# Gas_Sampler-Motor.net
KiCad netlist of a schematic drawn in Altium Designer
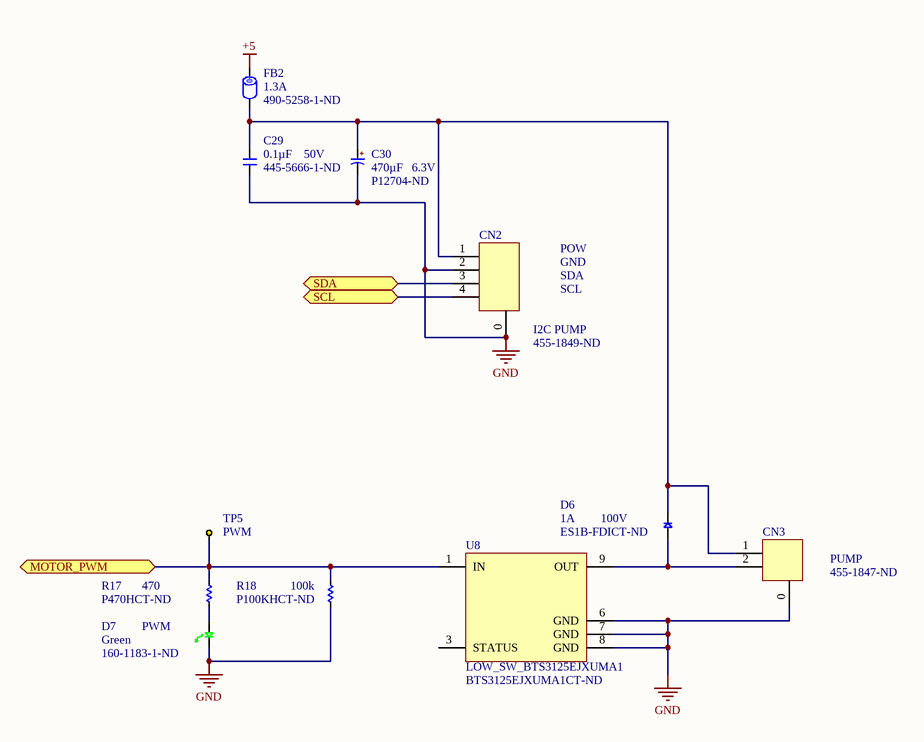
[diagram p0: Gas_Sampler-Motor.SchDoc]

(export (version "E")
  (design (tool "Eeschema 10.0.6"))
  (components
    (comp (ref "C29")
      (value "0.1µF")
      (footprint "C0603")
      (description "CAP CER 0.1UF 50V 10% X7R 0603")
      (fields
        (field (name "MANUFACTURER") "TDK Corporation")
        (field (name "MANUFACTURER PART NUMBER") "CGA3E2X7R1H104K080AA")
        (field (name "VOLTAGE - RATED") "50V")
        (field (name "SUPPLIER PART NUMBER 1") "445-5666-1-ND")
      )
      (libsource (lib "capacitor") (part "CAP_CER_0603_0.1UF_50V_10%_X7R"))
    )
    (comp (ref "C30")
      (value "470µF")
      (footprint "CAP_RADIAL_8MM_DIA_11.5MM_LEN_3.5MM_LEADSPACE")
      (description "CAP ALUM 470UF 6.3V 20% RADIAL")
      (fields
        (field (name "MANUFACTURER") "Panasonic Electronic Components")
        (field (name "MANUFACTURER PART NUMBER") "EEU-FC0J471")
        (field (name "VOLTAGE - RATED") "6.3V")
        (field (name "SUPPLIER PART NUMBER 1") "P12704-ND")
      )
      (libsource (lib "capacitor") (part "CAP_ALUM_470UF_6.3V_20%_RADIAL_8X11.5MM"))
    )
    (comp (ref "CN2")
      (value "I2C PUMP")
      (footprint "JST_PA_S04B-PASK-2")
      (description "CONN HEADER PA 4POS SIDE 2MM TIN")
      (fields
        (field (name "MANUFACTURER") "JST Sales America Inc.")
        (field (name "MANUFACTURER PART NUMBER") "S04B-PASK-2(LF)(SN)")
        (field (name "SUPPLIER PART NUMBER 1") "455-1849-ND")
      )
      (libsource (lib "jst pa") (part "JST_PA_RA_TH_GUIDE_4POS"))
    )
    (comp (ref "CN3")
      (value "PUMP")
      (footprint "JST_PA_S02B-PASK-2")
      (description "CONN HEADER PA 2POS SIDE 2MM TIN")
      (fields
        (field (name "MANUFACTURER") "JST Sales America Inc.")
        (field (name "MANUFACTURER PART NUMBER") "S02B-PASK-2(LF)(SN)")
        (field (name "SUPPLIER PART NUMBER 1") "455-1847-ND")
      )
      (libsource (lib "jst pa") (part "JST_PA_RA_TH_GUIDE_2POS"))
    )
    (comp (ref "D6")
      (value "DIODE_ES1B-FDICT-ND")
      (footprint "SMA")
      (description "DIODE SUPER FAST 100V 1A SMA")
      (fields
        (field (name "MANUFACTURER") "Diodes Inc")
        (field (name "MANUFACTURER PART NUMBER") "ES1B-13-F")
        (field (name "VOLTAGE - DC REVERSE (VR) (MAX)") "100V")
        (field (name "CURRENT - AVERAGE RECTIFIED (IO)") "1A")
        (field (name "SUPPLIER PART NUMBER 1") "ES1B-FDICT-ND")
      )
      (libsource (lib "diode") (part "DIODE_ES1B-FDICT-ND"))
    )
    (comp (ref "D7")
      (value "PWM")
      (footprint "LED_0603_GREEN")
      (description "LED GREEN CLEAR 0603 SMD")
      (fields
        (field (name "MANUFACTURER") "Lite-On Inc")
        (field (name "MANUFACTURER PART NUMBER") "LTST-C190GKT")
        (field (name "COLOR") "Green")
        (field (name "SUPPLIER PART NUMBER 1") "160-1183-1-ND")
      )
      (libsource (lib "diode") (part "LED_0603_GREEN_LG_LTST-C190GKT"))
    )
    (comp (ref "FB2")
      (value "FERRITE_BEAD_0603_1.3A_600_OHM")
      (footprint "R0603")
      (description "FERRITE BEAD 600 OHM 0603 1LN")
      (fields
        (field (name "MANUFACTURER") "Murata Electronics North America")
        (field (name "MANUFACTURER PART NUMBER") "BLM18KG601SN1D")
        (field (name "CURRENT RATING (MAX)") "1.3A")
        (field (name "SUPPLIER PART NUMBER 1") "490-5258-1-ND")
      )
      (libsource (lib "miscellaneous") (part "FERRITE_BEAD_0603_1.3A_600_OHM"))
    )
    (comp (ref "R17")
      (value "470")
      (footprint "R0603")
      (description "RES 470 OHM 1/10W 1% 0603 SMD")
      (fields
        (field (name "MANUFACTURER") "Panasonic Electronic Components")
        (field (name "MANUFACTURER PART NUMBER") "ERJ-3EKF4700V")
        (field (name "SUPPLIER PART NUMBER 1") "P470HCT-ND")
      )
      (libsource (lib "resistor") (part "RES_0603_470_OHM_1/10W_1%"))
    )
    (comp (ref "R18")
      (value "100k")
      (footprint "R0603")
      (description "RES 100K OHM 1/10W 1% 0603 SMD")
      (fields
        (field (name "MANUFACTURER") "Panasonic Electronic Components")
        (field (name "MANUFACTURER PART NUMBER") "ERJ-3EKF1003V")
        (field (name "SUPPLIER PART NUMBER 1") "P100KHCT-ND")
      )
      (libsource (lib "resistor") (part "RES_0603_100K_OHM_1/10W_1%"))
    )
    (comp (ref "TP5")
      (value "PWM")
      (footprint "TP_KEYSTONE_5001")
      (description "PC TEST POINT TH RING")
      (fields
        (field (name "MANUFACTURER") "Keystone Electronics")
        (field (name "MANUFACTURER PART NUMBER") "5001")
      )
      (libsource (lib "miscellaneous") (part "TEST_KEYSTONE5001"))
    )
    (comp (ref "U8")
      (value "LOW_SW_BTS3125EJXUMA1")
      (footprint "8SOIC150E")
      (description "IC PWR SWITCH N-CHAN 1:1 TDSO-8")
      (fields
        (field (name "MANUFACTURER") "Infineon Technologies")
        (field (name "MANUFACTURER PART NUMBER") "BTS3125EJXUMA1")
        (field (name "SUPPLIER PART NUMBER 1") "BTS3125EJXUMA1CT-ND")
      )
      (libsource (lib "ic_pmic") (part "LOW_SW_BTS3125EJXUMA1"))
    )
  )
  (nets
    (net (code "1") (name "+5") (class "Default")
      (node (ref "FB2") (pin "1") (pinfunction "1_1") (pintype "passive"))
    )
    (net (code "2") (name "/MOTOR_PWM") (class "Default")
      (node (ref "R17") (pin "2") (pintype "passive"))
      (node (ref "R18") (pin "2") (pintype "passive"))
      (node (ref "TP5") (pin "1") (pintype "passive"))
      (node (ref "U8") (pin "1") (pinfunction "IN_1") (pintype "passive"))
    )
    (net (code "3") (name "/SCL") (class "Default")
      (node (ref "CN2") (pin "4") (pinfunction "4_4") (pintype "passive"))
    )
    (net (code "4") (name "/SDA") (class "Default")
      (node (ref "CN2") (pin "3") (pinfunction "3_3") (pintype "passive"))
    )
    (net (code "5") (name "GND") (class "Default")
      (node (ref "C29") (pin "2") (pintype "passive"))
      (node (ref "C30") (pin "2") (pintype "passive"))
      (node (ref "CN2") (pin "0") (pinfunction "CHAS_0") (pintype "passive"))
      (node (ref "CN2") (pin "2") (pinfunction "2_2") (pintype "passive"))
      (node (ref "CN3") (pin "0") (pinfunction "CHAS_0") (pintype "passive"))
      (node (ref "D7") (pin "2") (pinfunction "CATHODE_2") (pintype "passive"))
      (node (ref "R18") (pin "1") (pintype "passive"))
      (node (ref "U8") (pin "6") (pinfunction "GND_6") (pintype "passive"))
      (node (ref "U8") (pin "7") (pinfunction "GND_7") (pintype "passive"))
      (node (ref "U8") (pin "8") (pinfunction "GND_8") (pintype "passive"))
    )
    (net (code "6") (name "Net-(C29-Pad1)") (class "Default")
      (node (ref "C29") (pin "1") (pintype "passive"))
      (node (ref "C30") (pin "1") (pintype "passive"))
      (node (ref "CN2") (pin "1") (pinfunction "1_1") (pintype "passive"))
      (node (ref "CN3") (pin "1") (pinfunction "1_1") (pintype "passive"))
      (node (ref "D6") (pin "2") (pintype "passive"))
      (node (ref "FB2") (pin "2") (pinfunction "2_2") (pintype "passive"))
    )
    (net (code "7") (name "Net-(D7-ANODE)") (class "Default")
      (node (ref "D7") (pin "1") (pinfunction "ANODE_1") (pintype "passive"))
      (node (ref "R17") (pin "1") (pintype "passive"))
    )
    (net (code "8") (name "Net-(U8-OUT)") (class "Default")
      (node (ref "CN3") (pin "2") (pinfunction "2_2") (pintype "passive"))
      (node (ref "D6") (pin "1") (pintype "passive"))
      (node (ref "U8") (pin "9") (pinfunction "OUT_9") (pintype "passive"))
    )
    (net (code "9") (name "unconnected-(U8-STATUS-Pad3)") (class "Default")
      (node (ref "U8") (pin "3") (pinfunction "STATUS_3") (pintype "passive"))
    )
  )
)
